# clock_led_face.net
KiCad netlist of a schematic drawn in Altium Designer
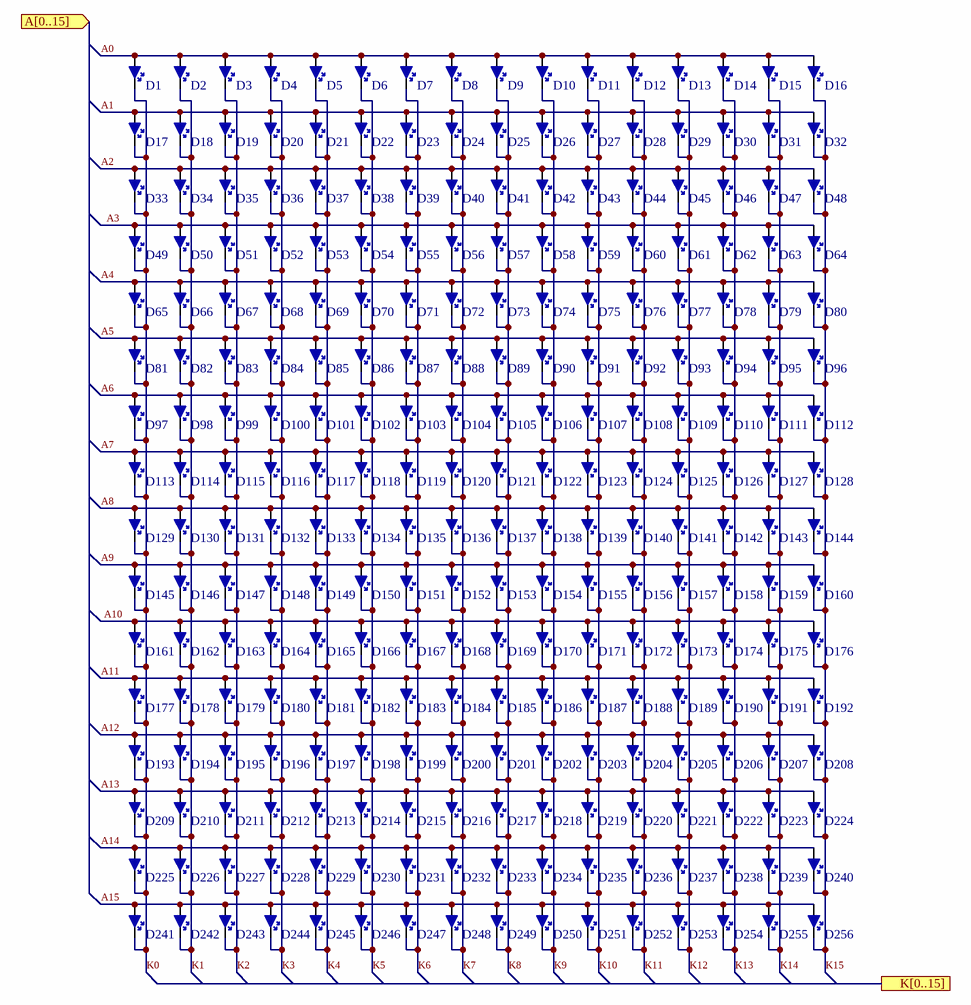
[diagram p0: clock_led_face.SchDoc]

(export (version "E")
  (design (tool "Eeschema 10.0.6"))
  (components
    (comp (ref "D1")
      (value "LED")
      (footprint "LED_0402")
      (description "Red 0402 SMD LED")
      (libsource (lib "") (part "LED_1"))
    )
    (comp (ref "D2")
      (value "LED")
      (footprint "LED_0402")
      (description "Red 0402 SMD LED")
      (libsource (lib "") (part "LED_1"))
    )
    (comp (ref "D3")
      (value "LED")
      (footprint "LED_0402")
      (description "Red 0402 SMD LED")
      (libsource (lib "") (part "LED_1"))
    )
    (comp (ref "D4")
      (value "LED")
      (footprint "LED_0402")
      (description "Red 0402 SMD LED")
      (libsource (lib "") (part "LED_1"))
    )
    (comp (ref "D5")
      (value "LED")
      (footprint "LED_0402")
      (description "Red 0402 SMD LED")
      (libsource (lib "") (part "LED_1"))
    )
    (comp (ref "D6")
      (value "LED")
      (footprint "LED_0402")
      (description "Red 0402 SMD LED")
      (libsource (lib "") (part "LED_1"))
    )
    (comp (ref "D7")
      (value "LED")
      (footprint "LED_0402")
      (description "Red 0402 SMD LED")
      (libsource (lib "") (part "LED_1"))
    )
    (comp (ref "D8")
      (value "LED")
      (footprint "LED_0402")
      (description "Red 0402 SMD LED")
      (libsource (lib "") (part "LED_1"))
    )
    (comp (ref "D9")
      (value "LED")
      (footprint "LED_0402")
      (description "Red 0402 SMD LED")
      (libsource (lib "") (part "LED_1"))
    )
    (comp (ref "D10")
      (value "LED")
      (footprint "LED_0402")
      (description "Red 0402 SMD LED")
      (libsource (lib "") (part "LED_1"))
    )
    (comp (ref "D11")
      (value "LED")
      (footprint "LED_0402")
      (description "Red 0402 SMD LED")
      (libsource (lib "") (part "LED_1"))
    )
    (comp (ref "D12")
      (value "LED")
      (footprint "LED_0402")
      (description "Red 0402 SMD LED")
      (libsource (lib "") (part "LED_1"))
    )
    (comp (ref "D13")
      (value "LED")
      (footprint "LED_0402")
      (description "Red 0402 SMD LED")
      (libsource (lib "") (part "LED_1"))
    )
    (comp (ref "D14")
      (value "LED")
      (footprint "LED_0402")
      (description "Red 0402 SMD LED")
      (libsource (lib "") (part "LED_1"))
    )
    (comp (ref "D15")
      (value "LED")
      (footprint "LED_0402")
      (description "Red 0402 SMD LED")
      (libsource (lib "") (part "LED_1"))
    )
    (comp (ref "D16")
      (value "LED")
      (footprint "LED_0402")
      (description "Red 0402 SMD LED")
      (libsource (lib "") (part "LED_1"))
    )
    (comp (ref "D17")
      (value "LED")
      (footprint "LED_0402")
      (description "Red 0402 SMD LED")
      (libsource (lib "") (part "LED_1"))
    )
    (comp (ref "D18")
      (value "LED")
      (footprint "LED_0402")
      (description "Red 0402 SMD LED")
      (libsource (lib "") (part "LED_1"))
    )
    (comp (ref "D19")
      (value "LED")
      (footprint "LED_0402")
      (description "Red 0402 SMD LED")
      (libsource (lib "") (part "LED_1"))
    )
    (comp (ref "D20")
      (value "LED")
      (footprint "LED_0402")
      (description "Red 0402 SMD LED")
      (libsource (lib "") (part "LED_1"))
    )
    (comp (ref "D21")
      (value "LED")
      (footprint "LED_0402")
      (description "Red 0402 SMD LED")
      (libsource (lib "") (part "LED_1"))
    )
    (comp (ref "D22")
      (value "LED")
      (footprint "LED_0402")
      (description "Red 0402 SMD LED")
      (libsource (lib "") (part "LED_1"))
    )
    (comp (ref "D23")
      (value "LED")
      (footprint "LED_0402")
      (description "Red 0402 SMD LED")
      (libsource (lib "") (part "LED_1"))
    )
    (comp (ref "D24")
      (value "LED")
      (footprint "LED_0402")
      (description "Red 0402 SMD LED")
      (libsource (lib "") (part "LED_1"))
    )
    (comp (ref "D25")
      (value "LED")
      (footprint "LED_0402")
      (description "Red 0402 SMD LED")
      (libsource (lib "") (part "LED_1"))
    )
    (comp (ref "D26")
      (value "LED")
      (footprint "LED_0402")
      (description "Red 0402 SMD LED")
      (libsource (lib "") (part "LED_1"))
    )
    (comp (ref "D27")
      (value "LED")
      (footprint "LED_0402")
      (description "Red 0402 SMD LED")
      (libsource (lib "") (part "LED_1"))
    )
    (comp (ref "D28")
      (value "LED")
      (footprint "LED_0402")
      (description "Red 0402 SMD LED")
      (libsource (lib "") (part "LED_1"))
    )
    (comp (ref "D29")
      (value "LED")
      (footprint "LED_0402")
      (description "Red 0402 SMD LED")
      (libsource (lib "") (part "LED_1"))
    )
    (comp (ref "D30")
      (value "LED")
      (footprint "LED_0402")
      (description "Red 0402 SMD LED")
      (libsource (lib "") (part "LED_1"))
    )
    (comp (ref "D31")
      (value "LED")
      (footprint "LED_0402")
      (description "Red 0402 SMD LED")
      (libsource (lib "") (part "LED_1"))
    )
    (comp (ref "D32")
      (value "LED")
      (footprint "LED_0402")
      (description "Red 0402 SMD LED")
      (libsource (lib "") (part "LED_1"))
    )
    (comp (ref "D33")
      (value "LED")
      (footprint "LED_0402")
      (description "Red 0402 SMD LED")
      (libsource (lib "") (part "LED_1"))
    )
    (comp (ref "D34")
      (value "LED")
      (footprint "LED_0402")
      (description "Red 0402 SMD LED")
      (libsource (lib "") (part "LED_1"))
    )
    (comp (ref "D35")
      (value "LED")
      (footprint "LED_0402")
      (description "Red 0402 SMD LED")
      (libsource (lib "") (part "LED_1"))
    )
    (comp (ref "D36")
      (value "LED")
      (footprint "LED_0402")
      (description "Red 0402 SMD LED")
      (libsource (lib "") (part "LED_1"))
    )
    (comp (ref "D37")
      (value "LED")
      (footprint "LED_0402")
      (description "Red 0402 SMD LED")
      (libsource (lib "") (part "LED_1"))
    )
    (comp (ref "D38")
      (value "LED")
      (footprint "LED_0402")
      (description "Red 0402 SMD LED")
      (libsource (lib "") (part "LED_1"))
    )
    (comp (ref "D39")
      (value "LED")
      (footprint "LED_0402")
      (description "Red 0402 SMD LED")
      (libsource (lib "") (part "LED_1"))
    )
    (comp (ref "D40")
      (value "LED")
      (footprint "LED_0402")
      (description "Red 0402 SMD LED")
      (libsource (lib "") (part "LED_1"))
    )
    (comp (ref "D41")
      (value "LED")
      (footprint "LED_0402")
      (description "Red 0402 SMD LED")
      (libsource (lib "") (part "LED_1"))
    )
    (comp (ref "D42")
      (value "LED")
      (footprint "LED_0402")
      (description "Red 0402 SMD LED")
      (libsource (lib "") (part "LED_1"))
    )
    (comp (ref "D43")
      (value "LED")
      (footprint "LED_0402")
      (description "Red 0402 SMD LED")
      (libsource (lib "") (part "LED_1"))
    )
    (comp (ref "D44")
      (value "LED")
      (footprint "LED_0402")
      (description "Red 0402 SMD LED")
      (libsource (lib "") (part "LED_1"))
    )
    (comp (ref "D45")
      (value "LED")
      (footprint "LED_0402")
      (description "Red 0402 SMD LED")
      (libsource (lib "") (part "LED_1"))
    )
    (comp (ref "D46")
      (value "LED")
      (footprint "LED_0402")
      (description "Red 0402 SMD LED")
      (libsource (lib "") (part "LED_1"))
    )
    (comp (ref "D47")
      (value "LED")
      (footprint "LED_0402")
      (description "Red 0402 SMD LED")
      (libsource (lib "") (part "LED_1"))
    )
    (comp (ref "D48")
      (value "LED")
      (footprint "LED_0402")
      (description "Red 0402 SMD LED")
      (libsource (lib "") (part "LED_1"))
    )
    (comp (ref "D49")
      (value "LED")
      (footprint "LED_0402")
      (description "Red 0402 SMD LED")
      (libsource (lib "") (part "LED_1"))
    )
    (comp (ref "D50")
      (value "LED")
      (footprint "LED_0402")
      (description "Red 0402 SMD LED")
      (libsource (lib "") (part "LED_1"))
    )
    (comp (ref "D51")
      (value "LED")
      (footprint "LED_0402")
      (description "Red 0402 SMD LED")
      (libsource (lib "") (part "LED_1"))
    )
    (comp (ref "D52")
      (value "LED")
      (footprint "LED_0402")
      (description "Red 0402 SMD LED")
      (libsource (lib "") (part "LED_1"))
    )
    (comp (ref "D53")
      (value "LED")
      (footprint "LED_0402")
      (description "Red 0402 SMD LED")
      (libsource (lib "") (part "LED_1"))
    )
    (comp (ref "D54")
      (value "LED")
      (footprint "LED_0402")
      (description "Red 0402 SMD LED")
      (libsource (lib "") (part "LED_1"))
    )
    (comp (ref "D55")
      (value "LED")
      (footprint "LED_0402")
      (description "Red 0402 SMD LED")
      (libsource (lib "") (part "LED_1"))
    )
    (comp (ref "D56")
      (value "LED")
      (footprint "LED_0402")
      (description "Red 0402 SMD LED")
      (libsource (lib "") (part "LED_1"))
    )
    (comp (ref "D57")
      (value "LED")
      (footprint "LED_0402")
      (description "Red 0402 SMD LED")
      (libsource (lib "") (part "LED_1"))
    )
    (comp (ref "D58")
      (value "LED")
      (footprint "LED_0402")
      (description "Red 0402 SMD LED")
      (libsource (lib "") (part "LED_1"))
    )
    (comp (ref "D59")
      (value "LED")
      (footprint "LED_0402")
      (description "Red 0402 SMD LED")
      (libsource (lib "") (part "LED_1"))
    )
    (comp (ref "D60")
      (value "LED")
      (footprint "LED_0402")
      (description "Red 0402 SMD LED")
      (libsource (lib "") (part "LED_1"))
    )
    (comp (ref "D61")
      (value "LED")
      (footprint "LED_0402")
      (description "Red 0402 SMD LED")
      (libsource (lib "") (part "LED_1"))
    )
    (comp (ref "D62")
      (value "LED")
      (footprint "LED_0402")
      (description "Red 0402 SMD LED")
      (libsource (lib "") (part "LED_1"))
    )
    (comp (ref "D63")
      (value "LED")
      (footprint "LED_0402")
      (description "Red 0402 SMD LED")
      (libsource (lib "") (part "LED_1"))
    )
    (comp (ref "D64")
      (value "LED")
      (footprint "LED_0402")
      (description "Red 0402 SMD LED")
      (libsource (lib "") (part "LED_1"))
    )
    (comp (ref "D65")
      (value "LED")
      (footprint "LED_0402")
      (description "Red 0402 SMD LED")
      (libsource (lib "") (part "LED_1"))
    )
    (comp (ref "D66")
      (value "LED")
      (footprint "LED_0402")
      (description "Red 0402 SMD LED")
      (libsource (lib "") (part "LED_1"))
    )
    (comp (ref "D67")
      (value "LED")
      (footprint "LED_0402")
      (description "Red 0402 SMD LED")
      (libsource (lib "") (part "LED_1"))
    )
    (comp (ref "D68")
      (value "LED")
      (footprint "LED_0402")
      (description "Red 0402 SMD LED")
      (libsource (lib "") (part "LED_1"))
    )
    (comp (ref "D69")
      (value "LED")
      (footprint "LED_0402")
      (description "Red 0402 SMD LED")
      (libsource (lib "") (part "LED_1"))
    )
    (comp (ref "D70")
      (value "LED")
      (footprint "LED_0402")
      (description "Red 0402 SMD LED")
      (libsource (lib "") (part "LED_1"))
    )
    (comp (ref "D71")
      (value "LED")
      (footprint "LED_0402")
      (description "Red 0402 SMD LED")
      (libsource (lib "") (part "LED_1"))
    )
    (comp (ref "D72")
      (value "LED")
      (footprint "LED_0402")
      (description "Red 0402 SMD LED")
      (libsource (lib "") (part "LED_1"))
    )
    (comp (ref "D73")
      (value "LED")
      (footprint "LED_0402")
      (description "Red 0402 SMD LED")
      (libsource (lib "") (part "LED_1"))
    )
    (comp (ref "D74")
      (value "LED")
      (footprint "LED_0402")
      (description "Red 0402 SMD LED")
      (libsource (lib "") (part "LED_1"))
    )
    (comp (ref "D75")
      (value "LED")
      (footprint "LED_0402")
      (description "Red 0402 SMD LED")
      (libsource (lib "") (part "LED_1"))
    )
    (comp (ref "D76")
      (value "LED")
      (footprint "LED_0402")
      (description "Red 0402 SMD LED")
      (libsource (lib "") (part "LED_1"))
    )
    (comp (ref "D77")
      (value "LED")
      (footprint "LED_0402")
      (description "Red 0402 SMD LED")
      (libsource (lib "") (part "LED_1"))
    )
    (comp (ref "D78")
      (value "LED")
      (footprint "LED_0402")
      (description "Red 0402 SMD LED")
      (libsource (lib "") (part "LED_1"))
    )
    (comp (ref "D79")
      (value "LED")
      (footprint "LED_0402")
      (description "Red 0402 SMD LED")
      (libsource (lib "") (part "LED_1"))
    )
    (comp (ref "D80")
      (value "LED")
      (footprint "LED_0402")
      (description "Red 0402 SMD LED")
      (libsource (lib "") (part "LED_1"))
    )
    (comp (ref "D81")
      (value "LED")
      (footprint "LED_0402")
      (description "Red 0402 SMD LED")
      (libsource (lib "") (part "LED_1"))
    )
    (comp (ref "D82")
      (value "LED")
      (footprint "LED_0402")
      (description "Red 0402 SMD LED")
      (libsource (lib "") (part "LED_1"))
    )
    (comp (ref "D83")
      (value "LED")
      (footprint "LED_0402")
      (description "Red 0402 SMD LED")
      (libsource (lib "") (part "LED_1"))
    )
    (comp (ref "D84")
      (value "LED")
      (footprint "LED_0402")
      (description "Red 0402 SMD LED")
      (libsource (lib "") (part "LED_1"))
    )
    (comp (ref "D85")
      (value "LED")
      (footprint "LED_0402")
      (description "Red 0402 SMD LED")
      (libsource (lib "") (part "LED_1"))
    )
    (comp (ref "D86")
      (value "LED")
      (footprint "LED_0402")
      (description "Red 0402 SMD LED")
      (libsource (lib "") (part "LED_1"))
    )
    (comp (ref "D87")
      (value "LED")
      (footprint "LED_0402")
      (description "Red 0402 SMD LED")
      (libsource (lib "") (part "LED_1"))
    )
    (comp (ref "D88")
      (value "LED")
      (footprint "LED_0402")
      (description "Red 0402 SMD LED")
      (libsource (lib "") (part "LED_1"))
    )
    (comp (ref "D89")
      (value "LED")
      (footprint "LED_0402")
      (description "Red 0402 SMD LED")
      (libsource (lib "") (part "LED_1"))
    )
    (comp (ref "D90")
      (value "LED")
      (footprint "LED_0402")
      (description "Red 0402 SMD LED")
      (libsource (lib "") (part "LED_1"))
    )
    (comp (ref "D91")
      (value "LED")
      (footprint "LED_0402")
      (description "Red 0402 SMD LED")
      (libsource (lib "") (part "LED_1"))
    )
    (comp (ref "D92")
      (value "LED")
      (footprint "LED_0402")
      (description "Red 0402 SMD LED")
      (libsource (lib "") (part "LED_1"))
    )
    (comp (ref "D93")
      (value "LED")
      (footprint "LED_0402")
      (description "Red 0402 SMD LED")
      (libsource (lib "") (part "LED_1"))
    )
    (comp (ref "D94")
      (value "LED")
      (footprint "LED_0402")
      (description "Red 0402 SMD LED")
      (libsource (lib "") (part "LED_1"))
    )
    (comp (ref "D95")
      (value "LED")
      (footprint "LED_0402")
      (description "Red 0402 SMD LED")
      (libsource (lib "") (part "LED_1"))
    )
    (comp (ref "D96")
      (value "LED")
      (footprint "LED_0402")
      (description "Red 0402 SMD LED")
      (libsource (lib "") (part "LED_1"))
    )
    (comp (ref "D97")
      (value "LED")
      (footprint "LED_0402")
      (description "Red 0402 SMD LED")
      (libsource (lib "") (part "LED_1"))
    )
    (comp (ref "D98")
      (value "LED")
      (footprint "LED_0402")
      (description "Red 0402 SMD LED")
      (libsource (lib "") (part "LED_1"))
    )
    (comp (ref "D99")
      (value "LED")
      (footprint "LED_0402")
      (description "Red 0402 SMD LED")
      (libsource (lib "") (part "LED_1"))
    )
    (comp (ref "D100")
      (value "LED")
      (footprint "LED_0402")
      (description "Red 0402 SMD LED")
      (libsource (lib "") (part "LED_1"))
    )
    (comp (ref "D101")
      (value "LED")
      (footprint "LED_0402")
      (description "Red 0402 SMD LED")
      (libsource (lib "") (part "LED_1"))
    )
    (comp (ref "D102")
      (value "LED")
      (footprint "LED_0402")
      (description "Red 0402 SMD LED")
      (libsource (lib "") (part "LED_1"))
    )
    (comp (ref "D103")
      (value "LED")
      (footprint "LED_0402")
      (description "Red 0402 SMD LED")
      (libsource (lib "") (part "LED_1"))
    )
    (comp (ref "D104")
      (value "LED")
      (footprint "LED_0402")
      (description "Red 0402 SMD LED")
      (libsource (lib "") (part "LED_1"))
    )
    (comp (ref "D105")
      (value "LED")
      (footprint "LED_0402")
      (description "Red 0402 SMD LED")
      (libsource (lib "") (part "LED_1"))
    )
    (comp (ref "D106")
      (value "LED")
      (footprint "LED_0402")
      (description "Red 0402 SMD LED")
      (libsource (lib "") (part "LED_1"))
    )
    (comp (ref "D107")
      (value "LED")
      (footprint "LED_0402")
      (description "Red 0402 SMD LED")
      (libsource (lib "") (part "LED_1"))
    )
    (comp (ref "D108")
      (value "LED")
      (footprint "LED_0402")
      (description "Red 0402 SMD LED")
      (libsource (lib "") (part "LED_1"))
    )
    (comp (ref "D109")
      (value "LED")
      (footprint "LED_0402")
      (description "Red 0402 SMD LED")
      (libsource (lib "") (part "LED_1"))
    )
    (comp (ref "D110")
      (value "LED")
      (footprint "LED_0402")
      (description "Red 0402 SMD LED")
      (libsource (lib "") (part "LED_1"))
    )
    (comp (ref "D111")
      (value "LED")
      (footprint "LED_0402")
      (description "Red 0402 SMD LED")
      (libsource (lib "") (part "LED_1"))
    )
    (comp (ref "D112")
      (value "LED")
      (footprint "LED_0402")
      (description "Red 0402 SMD LED")
      (libsource (lib "") (part "LED_1"))
    )
    (comp (ref "D113")
      (value "LED")
      (footprint "LED_0402")
      (description "Red 0402 SMD LED")
      (libsource (lib "") (part "LED_1"))
    )
    (comp (ref "D114")
      (value "LED")
      (footprint "LED_0402")
      (description "Red 0402 SMD LED")
      (libsource (lib "") (part "LED_1"))
    )
    (comp (ref "D115")
      (value "LED")
      (footprint "LED_0402")
      (description "Red 0402 SMD LED")
      (libsource (lib "") (part "LED_1"))
    )
    (comp (ref "D116")
      (value "LED")
      (footprint "LED_0402")
      (description "Red 0402 SMD LED")
      (libsource (lib "") (part "LED_1"))
    )
    (comp (ref "D117")
      (value "LED")
      (footprint "LED_0402")
      (description "Red 0402 SMD LED")
      (libsource (lib "") (part "LED_1"))
    )
    (comp (ref "D118")
      (value "LED")
      (footprint "LED_0402")
      (description "Red 0402 SMD LED")
      (libsource (lib "") (part "LED_1"))
    )
    (comp (ref "D119")
      (value "LED")
      (footprint "LED_0402")
      (description "Red 0402 SMD LED")
      (libsource (lib "") (part "LED_1"))
    )
    (comp (ref "D120")
      (value "LED")
      (footprint "LED_0402")
      (description "Red 0402 SMD LED")
      (libsource (lib "") (part "LED_1"))
    )
    (comp (ref "D121")
      (value "LED")
      (footprint "LED_0402")
      (description "Red 0402 SMD LED")
      (libsource (lib "") (part "LED_1"))
    )
    (comp (ref "D122")
      (value "LED")
      (footprint "LED_0402")
      (description "Red 0402 SMD LED")
      (libsource (lib "") (part "LED_1"))
    )
    (comp (ref "D123")
      (value "LED")
      (footprint "LED_0402")
      (description "Red 0402 SMD LED")
      (libsource (lib "") (part "LED_1"))
    )
    (comp (ref "D124")
      (value "LED")
      (footprint "LED_0402")
      (description "Red 0402 SMD LED")
      (libsource (lib "") (part "LED_1"))
    )
    (comp (ref "D125")
      (value "LED")
      (footprint "LED_0402")
      (description "Red 0402 SMD LED")
      (libsource (lib "") (part "LED_1"))
    )
    (comp (ref "D126")
      (value "LED")
      (footprint "LED_0402")
      (description "Red 0402 SMD LED")
      (libsource (lib "") (part "LED_1"))
    )
    (comp (ref "D127")
      (value "LED")
      (footprint "LED_0402")
      (description "Red 0402 SMD LED")
      (libsource (lib "") (part "LED_1"))
    )
    (comp (ref "D128")
      (value "LED")
      (footprint "LED_0402")
      (description "Red 0402 SMD LED")
      (libsource (lib "") (part "LED_1"))
    )
    (comp (ref "D129")
      (value "LED")
      (footprint "LED_0402")
      (description "Red 0402 SMD LED")
      (libsource (lib "") (part "LED_1"))
    )
    (comp (ref "D130")
      (value "LED")
      (footprint "LED_0402")
      (description "Red 0402 SMD LED")
      (libsource (lib "") (part "LED_1"))
    )
    (comp (ref "D131")
      (value "LED")
      (footprint "LED_0402")
      (description "Red 0402 SMD LED")
      (libsource (lib "") (part "LED_1"))
    )
    (comp (ref "D132")
      (value "LED")
      (footprint "LED_0402")
      (description "Red 0402 SMD LED")
      (libsource (lib "") (part "LED_1"))
    )
    (comp (ref "D133")
      (value "LED")
      (footprint "LED_0402")
      (description "Red 0402 SMD LED")
      (libsource (lib "") (part "LED_1"))
    )
    (comp (ref "D134")
      (value "LED")
      (footprint "LED_0402")
      (description "Red 0402 SMD LED")
      (libsource (lib "") (part "LED_1"))
    )
    (comp (ref "D135")
      (value "LED")
      (footprint "LED_0402")
      (description "Red 0402 SMD LED")
      (libsource (lib "") (part "LED_1"))
    )
    (comp (ref "D136")
      (value "LED")
      (footprint "LED_0402")
      (description "Red 0402 SMD LED")
      (libsource (lib "") (part "LED_1"))
    )
    (comp (ref "D137")
      (value "LED")
      (footprint "LED_0402")
      (description "Red 0402 SMD LED")
      (libsource (lib "") (part "LED_1"))
    )
    (comp (ref "D138")
      (value "LED")
      (footprint "LED_0402")
      (description "Red 0402 SMD LED")
      (libsource (lib "") (part "LED_1"))
    )
    (comp (ref "D139")
      (value "LED")
      (footprint "LED_0402")
      (description "Red 0402 SMD LED")
      (libsource (lib "") (part "LED_1"))
    )
    (comp (ref "D140")
      (value "LED")
      (footprint "LED_0402")
      (description "Red 0402 SMD LED")
      (libsource (lib "") (part "LED_1"))
    )
    (comp (ref "D141")
      (value "LED")
      (footprint "LED_0402")
      (description "Red 0402 SMD LED")
      (libsource (lib "") (part "LED_1"))
    )
    (comp (ref "D142")
      (value "LED")
      (footprint "LED_0402")
      (description "Red 0402 SMD LED")
      (libsource (lib "") (part "LED_1"))
    )
    (comp (ref "D143")
      (value "LED")
      (footprint "LED_0402")
      (description "Red 0402 SMD LED")
      (libsource (lib "") (part "LED_1"))
    )
    (comp (ref "D144")
      (value "LED")
      (footprint "LED_0402")
      (description "Red 0402 SMD LED")
      (libsource (lib "") (part "LED_1"))
    )
    (comp (ref "D145")
      (value "LED")
      (footprint "LED_0402")
      (description "Red 0402 SMD LED")
      (libsource (lib "") (part "LED_1"))
    )
    (comp (ref "D146")
      (value "LED")
      (footprint "LED_0402")
      (description "Red 0402 SMD LED")
      (libsource (lib "") (part "LED_1"))
    )
    (comp (ref "D147")
      (value "LED")
      (footprint "LED_0402")
      (description "Red 0402 SMD LED")
      (libsource (lib "") (part "LED_1"))
    )
    (comp (ref "D148")
      (value "LED")
      (footprint "LED_0402")
      (description "Red 0402 SMD LED")
      (libsource (lib "") (part "LED_1"))
    )
    (comp (ref "D149")
      (value "LED")
      (footprint "LED_0402")
      (description "Red 0402 SMD LED")
      (libsource (lib "") (part "LED_1"))
    )
    (comp (ref "D150")
      (value "LED")
      (footprint "LED_0402")
      (description "Red 0402 SMD LED")
      (libsource (lib "") (part "LED_1"))
    )
    (comp (ref "D151")
      (value "LED")
      (footprint "LED_0402")
      (description "Red 0402 SMD LED")
      (libsource (lib "") (part "LED_1"))
    )
    (comp (ref "D152")
      (value "LED")
      (footprint "LED_0402")
      (description "Red 0402 SMD LED")
      (libsource (lib "") (part "LED_1"))
    )
    (comp (ref "D153")
      (value "LED")
      (footprint "LED_0402")
      (description "Red 0402 SMD LED")
      (libsource (lib "") (part "LED_1"))
    )
    (comp (ref "D154")
      (value "LED")
      (footprint "LED_0402")
      (description "Red 0402 SMD LED")
      (libsource (lib "") (part "LED_1"))
    )
    (comp (ref "D155")
      (value "LED")
      (footprint "LED_0402")
      (description "Red 0402 SMD LED")
      (libsource (lib "") (part "LED_1"))
    )
    (comp (ref "D156")
      (value "LED")
      (footprint "LED_0402")
      (description "Red 0402 SMD LED")
      (libsource (lib "") (part "LED_1"))
    )
    (comp (ref "D157")
      (value "LED")
      (footprint "LED_0402")
      (description "Red 0402 SMD LED")
      (libsource (lib "") (part "LED_1"))
    )
    (comp (ref "D158")
      (value "LED")
      (footprint "LED_0402")
      (description "Red 0402 SMD LED")
      (libsource (lib "") (part "LED_1"))
    )
    (comp (ref "D159")
      (value "LED")
      (footprint "LED_0402")
      (description "Red 0402 SMD LED")
      (libsource (lib "") (part "LED_1"))
    )
    (comp (ref "D160")
      (value "LED")
      (footprint "LED_0402")
      (description "Red 0402 SMD LED")
      (libsource (lib "") (part "LED_1"))
    )
    (comp (ref "D161")
      (value "LED")
      (footprint "LED_0402")
      (description "Red 0402 SMD LED")
      (libsource (lib "") (part "LED_1"))
    )
    (comp (ref "D162")
      (value "LED")
      (footprint "LED_0402")
      (description "Red 0402 SMD LED")
      (libsource (lib "") (part "LED_1"))
    )
    (comp (ref "D163")
      (value "LED")
      (footprint "LED_0402")
      (description "Red 0402 SMD LED")
      (libsource (lib "") (part "LED_1"))
    )
    (comp (ref "D164")
      (value "LED")
      (footprint "LED_0402")
      (description "Red 0402 SMD LED")
      (libsource (lib "") (part "LED_1"))
    )
    (comp (ref "D165")
      (value "LED")
      (footprint "LED_0402")
      (description "Red 0402 SMD LED")
      (libsource (lib "") (part "LED_1"))
    )
    (comp (ref "D166")
      (value "LED")
      (footprint "LED_0402")
      (description "Red 0402 SMD LED")
      (libsource (lib "") (part "LED_1"))
    )
    (comp (ref "D167")
      (value "LED")
      (footprint "LED_0402")
      (description "Red 0402 SMD LED")
      (libsource (lib "") (part "LED_1"))
    )
    (comp (ref "D168")
      (value "LED")
      (footprint "LED_0402")
      (description "Red 0402 SMD LED")
      (libsource (lib "") (part "LED_1"))
    )
    (comp (ref "D169")
      (value "LED")
      (footprint "LED_0402")
      (description "Red 0402 SMD LED")
      (libsource (lib "") (part "LED_1"))
    )
    (comp (ref "D170")
      (value "LED")
      (footprint "LED_0402")
      (description "Red 0402 SMD LED")
      (libsource (lib "") (part "LED_1"))
    )
    (comp (ref "D171")
      (value "LED")
      (footprint "LED_0402")
      (description "Red 0402 SMD LED")
      (libsource (lib "") (part "LED_1"))
    )
    (comp (ref "D172")
      (value "LED")
      (footprint "LED_0402")
      (description "Red 0402 SMD LED")
      (libsource (lib "") (part "LED_1"))
    )
    (comp (ref "D173")
      (value "LED")
      (footprint "LED_0402")
      (description "Red 0402 SMD LED")
      (libsource (lib "") (part "LED_1"))
    )
    (comp (ref "D174")
      (value "LED")
      (footprint "LED_0402")
      (description "Red 0402 SMD LED")
      (libsource (lib "") (part "LED_1"))
    )
    (comp (ref "D175")
      (value "LED")
      (footprint "LED_0402")
      (description "Red 0402 SMD LED")
      (libsource (lib "") (part "LED_1"))
    )
    (comp (ref "D176")
      (value "LED")
      (footprint "LED_0402")
      (description "Red 0402 SMD LED")
      (libsource (lib "") (part "LED_1"))
    )
    (comp (ref "D177")
      (value "LED")
      (footprint "LED_0402")
      (description "Red 0402 SMD LED")
      (libsource (lib "") (part "LED_1"))
    )
    (comp (ref "D178")
      (value "LED")
      (footprint "LED_0402")
      (description "Red 0402 SMD LED")
      (libsource (lib "") (part "LED_1"))
    )
    (comp (ref "D179")
      (value "LED")
      (footprint "LED_0402")
      (description "Red 0402 SMD LED")
      (libsource (lib "") (part "LED_1"))
    )
    (comp (ref "D180")
      (value "LED")
      (footprint "LED_0402")
      (description "Red 0402 SMD LED")
      (libsource (lib "") (part "LED_1"))
    )
    (comp (ref "D181")
      (value "LED")
      (footprint "LED_0402")
      (description "Red 0402 SMD LED")
      (libsource (lib "") (part "LED_1"))
    )
    (comp (ref "D182")
      (value "LED")
      (footprint "LED_0402")
      (description "Red 0402 SMD LED")
      (libsource (lib "") (part "LED_1"))
    )
    (comp (ref "D183")
      (value "LED")
      (footprint "LED_0402")
      (description "Red 0402 SMD LED")
      (libsource (lib "") (part "LED_1"))
    )
    (comp (ref "D184")
      (value "LED")
      (footprint "LED_0402")
      (description "Red 0402 SMD LED")
      (libsource (lib "") (part "LED_1"))
    )
    (comp (ref "D185")
      (value "LED")
      (footprint "LED_0402")
      (description "Red 0402 SMD LED")
      (libsource (lib "") (part "LED_1"))
    )
    (comp (ref "D186")
      (value "LED")
      (footprint "LED_0402")
      (description "Red 0402 SMD LED")
      (libsource (lib "") (part "LED_1"))
    )
    (comp (ref "D187")
      (value "LED")
      (footprint "LED_0402")
      (description "Red 0402 SMD LED")
      (libsource (lib "") (part "LED_1"))
    )
    (comp (ref "D188")
      (value "LED")
      (footprint "LED_0402")
      (description "Red 0402 SMD LED")
      (libsource (lib "") (part "LED_1"))
    )
    (comp (ref "D189")
      (value "LED")
      (footprint "LED_0402")
      (description "Red 0402 SMD LED")
      (libsource (lib "") (part "LED_1"))
    )
    (comp (ref "D190")
      (value "LED")
      (footprint "LED_0402")
      (description "Red 0402 SMD LED")
      (libsource (lib "") (part "LED_1"))
    )
    (comp (ref "D191")
      (value "LED")
      (footprint "LED_0402")
      (description "Red 0402 SMD LED")
      (libsource (lib "") (part "LED_1"))
    )
    (comp (ref "D192")
      (value "LED")
      (footprint "LED_0402")
      (description "Red 0402 SMD LED")
      (libsource (lib "") (part "LED_1"))
    )
    (comp (ref "D193")
      (value "LED")
      (footprint "LED_0402")
      (description "Red 0402 SMD LED")
      (libsource (lib "") (part "LED_1"))
    )
    (comp (ref "D194")
      (value "LED")
      (footprint "LED_0402")
      (description "Red 0402 SMD LED")
      (libsource (lib "") (part "LED_1"))
    )
    (comp (ref "D195")
      (value "LED")
      (footprint "LED_0402")
      (description "Red 0402 SMD LED")
      (libsource (lib "") (part "LED_1"))
    )
    (comp (ref "D196")
      (value "LED")
      (footprint "LED_0402")
      (description "Red 0402 SMD LED")
      (libsource (lib "") (part "LED_1"))
    )
    (comp (ref "D197")
      (value "LED")
      (footprint "LED_0402")
      (description "Red 0402 SMD LED")
      (libsource (lib "") (part "LED_1"))
    )
    (comp (ref "D198")
      (value "LED")
      (footprint "LED_0402")
      (description "Red 0402 SMD LED")
      (libsource (lib "") (part "LED_1"))
    )
    (comp (ref "D199")
      (value "LED")
      (footprint "LED_0402")
      (description "Red 0402 SMD LED")
      (libsource (lib "") (part "LED_1"))
    )
    (comp (ref "D200")
      (value "LED")
      (footprint "LED_0402")
      (description "Red 0402 SMD LED")
      (libsource (lib "") (part "LED_1"))
    )
    (comp (ref "D201")
      (value "LED")
      (footprint "LED_0402")
      (description "Red 0402 SMD LED")
      (libsource (lib "") (part "LED_1"))
    )
    (comp (ref "D202")
      (value "LED")
      (footprint "LED_0402")
      (description "Red 0402 SMD LED")
      (libsource (lib "") (part "LED_1"))
    )
    (comp (ref "D203")
      (value "LED")
      (footprint "LED_0402")
      (description "Red 0402 SMD LED")
      (libsource (lib "") (part "LED_1"))
    )
    (comp (ref "D204")
      (value "LED")
      (footprint "LED_0402")
      (description "Red 0402 SMD LED")
      (libsource (lib "") (part "LED_1"))
    )
    (comp (ref "D205")
      (value "LED")
      (footprint "LED_0402")
      (description "Red 0402 SMD LED")
      (libsource (lib "") (part "LED_1"))
    )
    (comp (ref "D206")
      (value "LED")
      (footprint "LED_0402")
      (description "Red 0402 SMD LED")
      (libsource (lib "") (part "LED_1"))
    )
    (comp (ref "D207")
      (value "LED")
      (footprint "LED_0402")
      (description "Red 0402 SMD LED")
      (libsource (lib "") (part "LED_1"))
    )
    (comp (ref "D208")
      (value "LED")
      (footprint "LED_0402")
      (description "Red 0402 SMD LED")
      (libsource (lib "") (part "LED_1"))
    )
    (comp (ref "D209")
      (value "LED")
      (footprint "LED_0402")
      (description "Red 0402 SMD LED")
      (libsource (lib "clock_led") (part "LED"))
    )
    (comp (ref "D210")
      (value "LED")
      (footprint "LED_0402")
      (description "Red 0402 SMD LED")
      (libsource (lib "clock_led") (part "LED"))
    )
    (comp (ref "D211")
      (value "LED")
      (footprint "LED_0402")
      (description "Red 0402 SMD LED")
      (libsource (lib "clock_led") (part "LED"))
    )
    (comp (ref "D212")
      (value "LED")
      (footprint "LED_0402")
      (description "Red 0402 SMD LED")
      (libsource (lib "clock_led") (part "LED"))
    )
    (comp (ref "D213")
      (value "LED")
      (footprint "LED_0402")
      (description "Red 0402 SMD LED")
      (libsource (lib "clock_led") (part "LED"))
    )
    (comp (ref "D214")
      (value "LED")
      (footprint "LED_0402")
      (description "Red 0402 SMD LED")
      (libsource (lib "clock_led") (part "LED"))
    )
    (comp (ref "D215")
      (value "LED")
      (footprint "LED_0402")
      (description "Red 0402 SMD LED")
      (libsource (lib "clock_led") (part "LED"))
    )
    (comp (ref "D216")
      (value "LED")
      (footprint "LED_0402")
      (description "Red 0402 SMD LED")
      (libsource (lib "clock_led") (part "LED"))
    )
    (comp (ref "D217")
      (value "LED")
      (footprint "LED_0402")
      (description "Red 0402 SMD LED")
      (libsource (lib "clock_led") (part "LED"))
    )
    (comp (ref "D218")
      (value "LED")
      (footprint "LED_0402")
      (description "Red 0402 SMD LED")
      (libsource (lib "clock_led") (part "LED"))
    )
    (comp (ref "D219")
      (value "LED")
      (footprint "LED_0402")
      (description "Red 0402 SMD LED")
      (libsource (lib "clock_led") (part "LED"))
    )
    (comp (ref "D220")
      (value "LED")
      (footprint "LED_0402")
      (description "Red 0402 SMD LED")
      (libsource (lib "clock_led") (part "LED"))
    )
    (comp (ref "D221")
      (value "LED")
      (footprint "LED_0402")
      (description "Red 0402 SMD LED")
      (libsource (lib "clock_led") (part "LED"))
    )
    (comp (ref "D222")
      (value "LED")
      (footprint "LED_0402")
      (description "Red 0402 SMD LED")
      (libsource (lib "clock_led") (part "LED"))
    )
    (comp (ref "D223")
      (value "LED")
      (footprint "LED_0402")
      (description "Red 0402 SMD LED")
      (libsource (lib "clock_led") (part "LED"))
    )
    (comp (ref "D224")
      (value "LED")
      (footprint "LED_0402")
      (description "Red 0402 SMD LED")
      (libsource (lib "clock_led") (part "LED"))
    )
    (comp (ref "D225")
      (value "LED")
      (footprint "LED_0402")
      (description "Red 0402 SMD LED")
      (libsource (lib "") (part "LED_2"))
    )
    (comp (ref "D226")
      (value "LED")
      (footprint "LED_0402")
      (description "Red 0402 SMD LED")
      (libsource (lib "") (part "LED_2"))
    )
    (comp (ref "D227")
      (value "LED")
      (footprint "LED_0402")
      (description "Red 0402 SMD LED")
      (libsource (lib "") (part "LED_2"))
    )
    (comp (ref "D228")
      (value "LED")
      (footprint "LED_0402")
      (description "Red 0402 SMD LED")
      (libsource (lib "") (part "LED_2"))
    )
    (comp (ref "D229")
      (value "LED")
      (footprint "LED_0402")
      (description "Red 0402 SMD LED")
      (libsource (lib "") (part "LED_2"))
    )
    (comp (ref "D230")
      (value "LED")
      (footprint "LED_0402")
      (description "Red 0402 SMD LED")
      (libsource (lib "") (part "LED_2"))
    )
    (comp (ref "D231")
      (value "LED")
      (footprint "LED_0402")
      (description "Red 0402 SMD LED")
      (libsource (lib "") (part "LED_2"))
    )
    (comp (ref "D232")
      (value "LED")
      (footprint "LED_0402")
      (description "Red 0402 SMD LED")
      (libsource (lib "") (part "LED_2"))
    )
    (comp (ref "D233")
      (value "LED")
      (footprint "LED_0402")
      (description "Red 0402 SMD LED")
      (libsource (lib "") (part "LED_2"))
    )
    (comp (ref "D234")
      (value "LED")
      (footprint "LED_0402")
      (description "Red 0402 SMD LED")
      (libsource (lib "") (part "LED_2"))
    )
    (comp (ref "D235")
      (value "LED")
      (footprint "LED_0402")
      (description "Red 0402 SMD LED")
      (libsource (lib "") (part "LED_2"))
    )
    (comp (ref "D236")
      (value "LED")
      (footprint "LED_0402")
      (description "Red 0402 SMD LED")
      (libsource (lib "") (part "LED_2"))
    )
    (comp (ref "D237")
      (value "LED")
      (footprint "LED_0402")
      (description "Red 0402 SMD LED")
      (libsource (lib "") (part "LED_2"))
    )
    (comp (ref "D238")
      (value "LED")
      (footprint "LED_0402")
      (description "Red 0402 SMD LED")
      (libsource (lib "") (part "LED_2"))
    )
    (comp (ref "D239")
      (value "LED")
      (footprint "LED_0402")
      (description "Red 0402 SMD LED")
      (libsource (lib "") (part "LED_2"))
    )
    (comp (ref "D240")
      (value "LED")
      (footprint "LED_0402")
      (description "Red 0402 SMD LED")
      (libsource (lib "") (part "LED_2"))
    )
    (comp (ref "D241")
      (value "LED")
      (footprint "LED_0402")
      (description "Red 0402 SMD LED")
      (libsource (lib "") (part "LED_2"))
    )
    (comp (ref "D242")
      (value "LED")
      (footprint "LED_0402")
      (description "Red 0402 SMD LED")
      (libsource (lib "") (part "LED_2"))
    )
    (comp (ref "D243")
      (value "LED")
      (footprint "LED_0402")
      (description "Red 0402 SMD LED")
      (libsource (lib "") (part "LED_2"))
    )
    (comp (ref "D244")
      (value "LED")
      (footprint "LED_0402")
      (description "Red 0402 SMD LED")
      (libsource (lib "") (part "LED_2"))
    )
    (comp (ref "D245")
      (value "LED")
      (footprint "LED_0402")
      (description "Red 0402 SMD LED")
      (libsource (lib "") (part "LED_2"))
    )
    (comp (ref "D246")
      (value "LED")
      (footprint "LED_0402")
      (description "Red 0402 SMD LED")
      (libsource (lib "") (part "LED_2"))
    )
    (comp (ref "D247")
      (value "LED")
      (footprint "LED_0402")
      (description "Red 0402 SMD LED")
      (libsource (lib "") (part "LED_2"))
    )
    (comp (ref "D248")
      (value "LED")
      (footprint "LED_0402")
      (description "Red 0402 SMD LED")
      (libsource (lib "") (part "LED_2"))
    )
    (comp (ref "D249")
      (value "LED")
      (footprint "LED_0402")
      (description "Red 0402 SMD LED")
      (libsource (lib "") (part "LED_2"))
    )
    (comp (ref "D250")
      (value "LED")
      (footprint "LED_0402")
      (description "Red 0402 SMD LED")
      (libsource (lib "") (part "LED_2"))
    )
    (comp (ref "D251")
      (value "LED")
      (footprint "LED_0402")
      (description "Red 0402 SMD LED")
      (libsource (lib "") (part "LED_2"))
    )
    (comp (ref "D252")
      (value "LED")
      (footprint "LED_0402")
      (description "Red 0402 SMD LED")
      (libsource (lib "") (part "LED_2"))
    )
    (comp (ref "D253")
      (value "LED")
      (footprint "LED_0402")
      (description "Red 0402 SMD LED")
      (libsource (lib "") (part "LED_2"))
    )
    (comp (ref "D254")
      (value "LED")
      (footprint "LED_0402")
      (description "Red 0402 SMD LED")
      (libsource (lib "") (part "LED_2"))
    )
    (comp (ref "D255")
      (value "LED")
      (footprint "LED_0402")
      (description "Red 0402 SMD LED")
      (libsource (lib "") (part "LED_2"))
    )
    (comp (ref "D256")
      (value "LED")
      (footprint "LED_0402")
      (description "Red 0402 SMD LED")
      (libsource (lib "") (part "LED_2"))
    )
  )
  (nets
    (net (code "1") (name "/A0") (class "Default")
      (node (ref "D1") (pin "2") (pinfunction "A_2") (pintype "passive"))
      (node (ref "D10") (pin "2") (pinfunction "A_2") (pintype "passive"))
      (node (ref "D11") (pin "2") (pinfunction "A_2") (pintype "passive"))
      (node (ref "D12") (pin "2") (pinfunction "A_2") (pintype "passive"))
      (node (ref "D13") (pin "2") (pinfunction "A_2") (pintype "passive"))
      (node (ref "D14") (pin "2") (pinfunction "A_2") (pintype "passive"))
      (node (ref "D15") (pin "2") (pinfunction "A_2") (pintype "passive"))
      (node (ref "D16") (pin "2") (pinfunction "A_2") (pintype "passive"))
      (node (ref "D2") (pin "2") (pinfunction "A_2") (pintype "passive"))
      (node (ref "D3") (pin "2") (pinfunction "A_2") (pintype "passive"))
      (node (ref "D4") (pin "2") (pinfunction "A_2") (pintype "passive"))
      (node (ref "D5") (pin "2") (pinfunction "A_2") (pintype "passive"))
      (node (ref "D6") (pin "2") (pinfunction "A_2") (pintype "passive"))
      (node (ref "D7") (pin "2") (pinfunction "A_2") (pintype "passive"))
      (node (ref "D8") (pin "2") (pinfunction "A_2") (pintype "passive"))
      (node (ref "D9") (pin "2") (pinfunction "A_2") (pintype "passive"))
    )
    (net (code "2") (name "/A1") (class "Default")
      (node (ref "D17") (pin "2") (pinfunction "A_2") (pintype "passive"))
      (node (ref "D18") (pin "2") (pinfunction "A_2") (pintype "passive"))
      (node (ref "D19") (pin "2") (pinfunction "A_2") (pintype "passive"))
      (node (ref "D20") (pin "2") (pinfunction "A_2") (pintype "passive"))
      (node (ref "D21") (pin "2") (pinfunction "A_2") (pintype "passive"))
      (node (ref "D22") (pin "2") (pinfunction "A_2") (pintype "passive"))
      (node (ref "D23") (pin "2") (pinfunction "A_2") (pintype "passive"))
      (node (ref "D24") (pin "2") (pinfunction "A_2") (pintype "passive"))
      (node (ref "D25") (pin "2") (pinfunction "A_2") (pintype "passive"))
      (node (ref "D26") (pin "2") (pinfunction "A_2") (pintype "passive"))
      (node (ref "D27") (pin "2") (pinfunction "A_2") (pintype "passive"))
      (node (ref "D28") (pin "2") (pinfunction "A_2") (pintype "passive"))
      (node (ref "D29") (pin "2") (pinfunction "A_2") (pintype "passive"))
      (node (ref "D30") (pin "2") (pinfunction "A_2") (pintype "passive"))
      (node (ref "D31") (pin "2") (pinfunction "A_2") (pintype "passive"))
      (node (ref "D32") (pin "2") (pinfunction "A_2") (pintype "passive"))
    )
    (net (code "3") (name "/A2") (class "Default")
      (node (ref "D33") (pin "2") (pinfunction "A_2") (pintype "passive"))
      (node (ref "D34") (pin "2") (pinfunction "A_2") (pintype "passive"))
      (node (ref "D35") (pin "2") (pinfunction "A_2") (pintype "passive"))
      (node (ref "D36") (pin "2") (pinfunction "A_2") (pintype "passive"))
      (node (ref "D37") (pin "2") (pinfunction "A_2") (pintype "passive"))
      (node (ref "D38") (pin "2") (pinfunction "A_2") (pintype "passive"))
      (node (ref "D39") (pin "2") (pinfunction "A_2") (pintype "passive"))
      (node (ref "D40") (pin "2") (pinfunction "A_2") (pintype "passive"))
      (node (ref "D41") (pin "2") (pinfunction "A_2") (pintype "passive"))
      (node (ref "D42") (pin "2") (pinfunction "A_2") (pintype "passive"))
      (node (ref "D43") (pin "2") (pinfunction "A_2") (pintype "passive"))
      (node (ref "D44") (pin "2") (pinfunction "A_2") (pintype "passive"))
      (node (ref "D45") (pin "2") (pinfunction "A_2") (pintype "passive"))
      (node (ref "D46") (pin "2") (pinfunction "A_2") (pintype "passive"))
      (node (ref "D47") (pin "2") (pinfunction "A_2") (pintype "passive"))
      (node (ref "D48") (pin "2") (pinfunction "A_2") (pintype "passive"))
    )
    (net (code "4") (name "/A3") (class "Default")
      (node (ref "D49") (pin "2") (pinfunction "A_2") (pintype "passive"))
      (node (ref "D50") (pin "2") (pinfunction "A_2") (pintype "passive"))
      (node (ref "D51") (pin "2") (pinfunction "A_2") (pintype "passive"))
      (node (ref "D52") (pin "2") (pinfunction "A_2") (pintype "passive"))
      (node (ref "D53") (pin "2") (pinfunction "A_2") (pintype "passive"))
      (node (ref "D54") (pin "2") (pinfunction "A_2") (pintype "passive"))
      (node (ref "D55") (pin "2") (pinfunction "A_2") (pintype "passive"))
      (node (ref "D56") (pin "2") (pinfunction "A_2") (pintype "passive"))
      (node (ref "D57") (pin "2") (pinfunction "A_2") (pintype "passive"))
      (node (ref "D58") (pin "2") (pinfunction "A_2") (pintype "passive"))
      (node (ref "D59") (pin "2") (pinfunction "A_2") (pintype "passive"))
      (node (ref "D60") (pin "2") (pinfunction "A_2") (pintype "passive"))
      (node (ref "D61") (pin "2") (pinfunction "A_2") (pintype "passive"))
      (node (ref "D62") (pin "2") (pinfunction "A_2") (pintype "passive"))
      (node (ref "D63") (pin "2") (pinfunction "A_2") (pintype "passive"))
      (node (ref "D64") (pin "2") (pinfunction "A_2") (pintype "passive"))
    )
    (net (code "5") (name "/A4") (class "Default")
      (node (ref "D65") (pin "2") (pinfunction "A_2") (pintype "passive"))
      (node (ref "D66") (pin "2") (pinfunction "A_2") (pintype "passive"))
      (node (ref "D67") (pin "2") (pinfunction "A_2") (pintype "passive"))
      (node (ref "D68") (pin "2") (pinfunction "A_2") (pintype "passive"))
      (node (ref "D69") (pin "2") (pinfunction "A_2") (pintype "passive"))
      (node (ref "D70") (pin "2") (pinfunction "A_2") (pintype "passive"))
      (node (ref "D71") (pin "2") (pinfunction "A_2") (pintype "passive"))
      (node (ref "D72") (pin "2") (pinfunction "A_2") (pintype "passive"))
      (node (ref "D73") (pin "2") (pinfunction "A_2") (pintype "passive"))
      (node (ref "D74") (pin "2") (pinfunction "A_2") (pintype "passive"))
      (node (ref "D75") (pin "2") (pinfunction "A_2") (pintype "passive"))
      (node (ref "D76") (pin "2") (pinfunction "A_2") (pintype "passive"))
      (node (ref "D77") (pin "2") (pinfunction "A_2") (pintype "passive"))
      (node (ref "D78") (pin "2") (pinfunction "A_2") (pintype "passive"))
      (node (ref "D79") (pin "2") (pinfunction "A_2") (pintype "passive"))
      (node (ref "D80") (pin "2") (pinfunction "A_2") (pintype "passive"))
    )
    (net (code "6") (name "/A5") (class "Default")
      (node (ref "D81") (pin "2") (pinfunction "A_2") (pintype "passive"))
      (node (ref "D82") (pin "2") (pinfunction "A_2") (pintype "passive"))
      (node (ref "D83") (pin "2") (pinfunction "A_2") (pintype "passive"))
      (node (ref "D84") (pin "2") (pinfunction "A_2") (pintype "passive"))
      (node (ref "D85") (pin "2") (pinfunction "A_2") (pintype "passive"))
      (node (ref "D86") (pin "2") (pinfunction "A_2") (pintype "passive"))
      (node (ref "D87") (pin "2") (pinfunction "A_2") (pintype "passive"))
      (node (ref "D88") (pin "2") (pinfunction "A_2") (pintype "passive"))
      (node (ref "D89") (pin "2") (pinfunction "A_2") (pintype "passive"))
      (node (ref "D90") (pin "2") (pinfunction "A_2") (pintype "passive"))
      (node (ref "D91") (pin "2") (pinfunction "A_2") (pintype "passive"))
      (node (ref "D92") (pin "2") (pinfunction "A_2") (pintype "passive"))
      (node (ref "D93") (pin "2") (pinfunction "A_2") (pintype "passive"))
      (node (ref "D94") (pin "2") (pinfunction "A_2") (pintype "passive"))
      (node (ref "D95") (pin "2") (pinfunction "A_2") (pintype "passive"))
      (node (ref "D96") (pin "2") (pinfunction "A_2") (pintype "passive"))
    )
    (net (code "7") (name "/A6") (class "Default")
      (node (ref "D100") (pin "2") (pinfunction "A_2") (pintype "passive"))
      (node (ref "D101") (pin "2") (pinfunction "A_2") (pintype "passive"))
      (node (ref "D102") (pin "2") (pinfunction "A_2") (pintype "passive"))
      (node (ref "D103") (pin "2") (pinfunction "A_2") (pintype "passive"))
      (node (ref "D104") (pin "2") (pinfunction "A_2") (pintype "passive"))
      (node (ref "D105") (pin "2") (pinfunction "A_2") (pintype "passive"))
      (node (ref "D106") (pin "2") (pinfunction "A_2") (pintype "passive"))
      (node (ref "D107") (pin "2") (pinfunction "A_2") (pintype "passive"))
      (node (ref "D108") (pin "2") (pinfunction "A_2") (pintype "passive"))
      (node (ref "D109") (pin "2") (pinfunction "A_2") (pintype "passive"))
      (node (ref "D110") (pin "2") (pinfunction "A_2") (pintype "passive"))
      (node (ref "D111") (pin "2") (pinfunction "A_2") (pintype "passive"))
      (node (ref "D112") (pin "2") (pinfunction "A_2") (pintype "passive"))
      (node (ref "D97") (pin "2") (pinfunction "A_2") (pintype "passive"))
      (node (ref "D98") (pin "2") (pinfunction "A_2") (pintype "passive"))
      (node (ref "D99") (pin "2") (pinfunction "A_2") (pintype "passive"))
    )
    (net (code "8") (name "/A7") (class "Default")
      (node (ref "D113") (pin "2") (pinfunction "A_2") (pintype "passive"))
      (node (ref "D114") (pin "2") (pinfunction "A_2") (pintype "passive"))
      (node (ref "D115") (pin "2") (pinfunction "A_2") (pintype "passive"))
      (node (ref "D116") (pin "2") (pinfunction "A_2") (pintype "passive"))
      (node (ref "D117") (pin "2") (pinfunction "A_2") (pintype "passive"))
      (node (ref "D118") (pin "2") (pinfunction "A_2") (pintype "passive"))
      (node (ref "D119") (pin "2") (pinfunction "A_2") (pintype "passive"))
      (node (ref "D120") (pin "2") (pinfunction "A_2") (pintype "passive"))
      (node (ref "D121") (pin "2") (pinfunction "A_2") (pintype "passive"))
      (node (ref "D122") (pin "2") (pinfunction "A_2") (pintype "passive"))
      (node (ref "D123") (pin "2") (pinfunction "A_2") (pintype "passive"))
      (node (ref "D124") (pin "2") (pinfunction "A_2") (pintype "passive"))
      (node (ref "D125") (pin "2") (pinfunction "A_2") (pintype "passive"))
      (node (ref "D126") (pin "2") (pinfunction "A_2") (pintype "passive"))
      (node (ref "D127") (pin "2") (pinfunction "A_2") (pintype "passive"))
      (node (ref "D128") (pin "2") (pinfunction "A_2") (pintype "passive"))
    )
    (net (code "9") (name "/A8") (class "Default")
      (node (ref "D129") (pin "2") (pinfunction "A_2") (pintype "passive"))
      (node (ref "D130") (pin "2") (pinfunction "A_2") (pintype "passive"))
      (node (ref "D131") (pin "2") (pinfunction "A_2") (pintype "passive"))
      (node (ref "D132") (pin "2") (pinfunction "A_2") (pintype "passive"))
      (node (ref "D133") (pin "2") (pinfunction "A_2") (pintype "passive"))
      (node (ref "D134") (pin "2") (pinfunction "A_2") (pintype "passive"))
      (node (ref "D135") (pin "2") (pinfunction "A_2") (pintype "passive"))
      (node (ref "D136") (pin "2") (pinfunction "A_2") (pintype "passive"))
      (node (ref "D137") (pin "2") (pinfunction "A_2") (pintype "passive"))
      (node (ref "D138") (pin "2") (pinfunction "A_2") (pintype "passive"))
      (node (ref "D139") (pin "2") (pinfunction "A_2") (pintype "passive"))
      (node (ref "D140") (pin "2") (pinfunction "A_2") (pintype "passive"))
      (node (ref "D141") (pin "2") (pinfunction "A_2") (pintype "passive"))
      (node (ref "D142") (pin "2") (pinfunction "A_2") (pintype "passive"))
      (node (ref "D143") (pin "2") (pinfunction "A_2") (pintype "passive"))
      (node (ref "D144") (pin "2") (pinfunction "A_2") (pintype "passive"))
    )
    (net (code "10") (name "/A9") (class "Default")
      (node (ref "D145") (pin "2") (pinfunction "A_2") (pintype "passive"))
      (node (ref "D146") (pin "2") (pinfunction "A_2") (pintype "passive"))
      (node (ref "D147") (pin "2") (pinfunction "A_2") (pintype "passive"))
      (node (ref "D148") (pin "2") (pinfunction "A_2") (pintype "passive"))
      (node (ref "D149") (pin "2") (pinfunction "A_2") (pintype "passive"))
      (node (ref "D150") (pin "2") (pinfunction "A_2") (pintype "passive"))
      (node (ref "D151") (pin "2") (pinfunction "A_2") (pintype "passive"))
      (node (ref "D152") (pin "2") (pinfunction "A_2") (pintype "passive"))
      (node (ref "D153") (pin "2") (pinfunction "A_2") (pintype "passive"))
      (node (ref "D154") (pin "2") (pinfunction "A_2") (pintype "passive"))
      (node (ref "D155") (pin "2") (pinfunction "A_2") (pintype "passive"))
      (node (ref "D156") (pin "2") (pinfunction "A_2") (pintype "passive"))
      (node (ref "D157") (pin "2") (pinfunction "A_2") (pintype "passive"))
      (node (ref "D158") (pin "2") (pinfunction "A_2") (pintype "passive"))
      (node (ref "D159") (pin "2") (pinfunction "A_2") (pintype "passive"))
      (node (ref "D160") (pin "2") (pinfunction "A_2") (pintype "passive"))
    )
    (net (code "11") (name "/A10") (class "Default")
      (node (ref "D161") (pin "2") (pinfunction "A_2") (pintype "passive"))
      (node (ref "D162") (pin "2") (pinfunction "A_2") (pintype "passive"))
      (node (ref "D163") (pin "2") (pinfunction "A_2") (pintype "passive"))
      (node (ref "D164") (pin "2") (pinfunction "A_2") (pintype "passive"))
      (node (ref "D165") (pin "2") (pinfunction "A_2") (pintype "passive"))
      (node (ref "D166") (pin "2") (pinfunction "A_2") (pintype "passive"))
      (node (ref "D167") (pin "2") (pinfunction "A_2") (pintype "passive"))
      (node (ref "D168") (pin "2") (pinfunction "A_2") (pintype "passive"))
      (node (ref "D169") (pin "2") (pinfunction "A_2") (pintype "passive"))
      (node (ref "D170") (pin "2") (pinfunction "A_2") (pintype "passive"))
      (node (ref "D171") (pin "2") (pinfunction "A_2") (pintype "passive"))
      (node (ref "D172") (pin "2") (pinfunction "A_2") (pintype "passive"))
      (node (ref "D173") (pin "2") (pinfunction "A_2") (pintype "passive"))
      (node (ref "D174") (pin "2") (pinfunction "A_2") (pintype "passive"))
      (node (ref "D175") (pin "2") (pinfunction "A_2") (pintype "passive"))
      (node (ref "D176") (pin "2") (pinfunction "A_2") (pintype "passive"))
    )
    (net (code "12") (name "/A11") (class "Default")
      (node (ref "D177") (pin "2") (pinfunction "A_2") (pintype "passive"))
      (node (ref "D178") (pin "2") (pinfunction "A_2") (pintype "passive"))
      (node (ref "D179") (pin "2") (pinfunction "A_2") (pintype "passive"))
      (node (ref "D180") (pin "2") (pinfunction "A_2") (pintype "passive"))
      (node (ref "D181") (pin "2") (pinfunction "A_2") (pintype "passive"))
      (node (ref "D182") (pin "2") (pinfunction "A_2") (pintype "passive"))
      (node (ref "D183") (pin "2") (pinfunction "A_2") (pintype "passive"))
      (node (ref "D184") (pin "2") (pinfunction "A_2") (pintype "passive"))
      (node (ref "D185") (pin "2") (pinfunction "A_2") (pintype "passive"))
      (node (ref "D186") (pin "2") (pinfunction "A_2") (pintype "passive"))
      (node (ref "D187") (pin "2") (pinfunction "A_2") (pintype "passive"))
      (node (ref "D188") (pin "2") (pinfunction "A_2") (pintype "passive"))
      (node (ref "D189") (pin "2") (pinfunction "A_2") (pintype "passive"))
      (node (ref "D190") (pin "2") (pinfunction "A_2") (pintype "passive"))
      (node (ref "D191") (pin "2") (pinfunction "A_2") (pintype "passive"))
      (node (ref "D192") (pin "2") (pinfunction "A_2") (pintype "passive"))
    )
    (net (code "13") (name "/A12") (class "Default")
      (node (ref "D193") (pin "2") (pinfunction "A_2") (pintype "passive"))
      (node (ref "D194") (pin "2") (pinfunction "A_2") (pintype "passive"))
      (node (ref "D195") (pin "2") (pinfunction "A_2") (pintype "passive"))
      (node (ref "D196") (pin "2") (pinfunction "A_2") (pintype "passive"))
      (node (ref "D197") (pin "2") (pinfunction "A_2") (pintype "passive"))
      (node (ref "D198") (pin "2") (pinfunction "A_2") (pintype "passive"))
      (node (ref "D199") (pin "2") (pinfunction "A_2") (pintype "passive"))
      (node (ref "D200") (pin "2") (pinfunction "A_2") (pintype "passive"))
      (node (ref "D201") (pin "2") (pinfunction "A_2") (pintype "passive"))
      (node (ref "D202") (pin "2") (pinfunction "A_2") (pintype "passive"))
      (node (ref "D203") (pin "2") (pinfunction "A_2") (pintype "passive"))
      (node (ref "D204") (pin "2") (pinfunction "A_2") (pintype "passive"))
      (node (ref "D205") (pin "2") (pinfunction "A_2") (pintype "passive"))
      (node (ref "D206") (pin "2") (pinfunction "A_2") (pintype "passive"))
      (node (ref "D207") (pin "2") (pinfunction "A_2") (pintype "passive"))
      (node (ref "D208") (pin "2") (pinfunction "A_2") (pintype "passive"))
    )
    (net (code "14") (name "/A13") (class "Default")
      (node (ref "D209") (pin "2") (pinfunction "A_2") (pintype "passive"))
      (node (ref "D210") (pin "2") (pinfunction "A_2") (pintype "passive"))
      (node (ref "D211") (pin "2") (pinfunction "A_2") (pintype "passive"))
      (node (ref "D212") (pin "2") (pinfunction "A_2") (pintype "passive"))
      (node (ref "D213") (pin "2") (pinfunction "A_2") (pintype "passive"))
      (node (ref "D214") (pin "2") (pinfunction "A_2") (pintype "passive"))
      (node (ref "D215") (pin "2") (pinfunction "A_2") (pintype "passive"))
      (node (ref "D216") (pin "2") (pinfunction "A_2") (pintype "passive"))
      (node (ref "D217") (pin "2") (pinfunction "A_2") (pintype "passive"))
      (node (ref "D218") (pin "2") (pinfunction "A_2") (pintype "passive"))
      (node (ref "D219") (pin "2") (pinfunction "A_2") (pintype "passive"))
      (node (ref "D220") (pin "2") (pinfunction "A_2") (pintype "passive"))
      (node (ref "D221") (pin "2") (pinfunction "A_2") (pintype "passive"))
      (node (ref "D222") (pin "2") (pinfunction "A_2") (pintype "passive"))
      (node (ref "D223") (pin "2") (pinfunction "A_2") (pintype "passive"))
      (node (ref "D224") (pin "2") (pinfunction "A_2") (pintype "passive"))
    )
    (net (code "15") (name "/A14") (class "Default")
      (node (ref "D225") (pin "2") (pinfunction "A_2") (pintype "passive"))
      (node (ref "D226") (pin "2") (pinfunction "A_2") (pintype "passive"))
      (node (ref "D227") (pin "2") (pinfunction "A_2") (pintype "passive"))
      (node (ref "D228") (pin "2") (pinfunction "A_2") (pintype "passive"))
      (node (ref "D229") (pin "2") (pinfunction "A_2") (pintype "passive"))
      (node (ref "D230") (pin "2") (pinfunction "A_2") (pintype "passive"))
      (node (ref "D231") (pin "2") (pinfunction "A_2") (pintype "passive"))
      (node (ref "D232") (pin "2") (pinfunction "A_2") (pintype "passive"))
      (node (ref "D233") (pin "2") (pinfunction "A_2") (pintype "passive"))
      (node (ref "D234") (pin "2") (pinfunction "A_2") (pintype "passive"))
      (node (ref "D235") (pin "2") (pinfunction "A_2") (pintype "passive"))
      (node (ref "D236") (pin "2") (pinfunction "A_2") (pintype "passive"))
      (node (ref "D237") (pin "2") (pinfunction "A_2") (pintype "passive"))
      (node (ref "D238") (pin "2") (pinfunction "A_2") (pintype "passive"))
      (node (ref "D239") (pin "2") (pinfunction "A_2") (pintype "passive"))
      (node (ref "D240") (pin "2") (pinfunction "A_2") (pintype "passive"))
    )
    (net (code "16") (name "/A15") (class "Default")
      (node (ref "D241") (pin "2") (pinfunction "A_2") (pintype "passive"))
      (node (ref "D242") (pin "2") (pinfunction "A_2") (pintype "passive"))
      (node (ref "D243") (pin "2") (pinfunction "A_2") (pintype "passive"))
      (node (ref "D244") (pin "2") (pinfunction "A_2") (pintype "passive"))
      (node (ref "D245") (pin "2") (pinfunction "A_2") (pintype "passive"))
      (node (ref "D246") (pin "2") (pinfunction "A_2") (pintype "passive"))
      (node (ref "D247") (pin "2") (pinfunction "A_2") (pintype "passive"))
      (node (ref "D248") (pin "2") (pinfunction "A_2") (pintype "passive"))
      (node (ref "D249") (pin "2") (pinfunction "A_2") (pintype "passive"))
      (node (ref "D250") (pin "2") (pinfunction "A_2") (pintype "passive"))
      (node (ref "D251") (pin "2") (pinfunction "A_2") (pintype "passive"))
      (node (ref "D252") (pin "2") (pinfunction "A_2") (pintype "passive"))
      (node (ref "D253") (pin "2") (pinfunction "A_2") (pintype "passive"))
      (node (ref "D254") (pin "2") (pinfunction "A_2") (pintype "passive"))
      (node (ref "D255") (pin "2") (pinfunction "A_2") (pintype "passive"))
      (node (ref "D256") (pin "2") (pinfunction "A_2") (pintype "passive"))
    )
    (net (code "18") (name "/K0") (class "Default")
      (node (ref "D1") (pin "1") (pinfunction "C_1") (pintype "passive"))
      (node (ref "D113") (pin "1") (pinfunction "C_1") (pintype "passive"))
      (node (ref "D129") (pin "1") (pinfunction "C_1") (pintype "passive"))
      (node (ref "D145") (pin "1") (pinfunction "C_1") (pintype "passive"))
      (node (ref "D161") (pin "1") (pinfunction "C_1") (pintype "passive"))
      (node (ref "D17") (pin "1") (pinfunction "C_1") (pintype "passive"))
      (node (ref "D177") (pin "1") (pinfunction "C_1") (pintype "passive"))
      (node (ref "D193") (pin "1") (pinfunction "C_1") (pintype "passive"))
      (node (ref "D209") (pin "1") (pinfunction "C_1") (pintype "passive"))
      (node (ref "D225") (pin "1") (pinfunction "C_1") (pintype "passive"))
      (node (ref "D241") (pin "1") (pinfunction "C_1") (pintype "passive"))
      (node (ref "D33") (pin "1") (pinfunction "C_1") (pintype "passive"))
      (node (ref "D49") (pin "1") (pinfunction "C_1") (pintype "passive"))
      (node (ref "D65") (pin "1") (pinfunction "C_1") (pintype "passive"))
      (node (ref "D81") (pin "1") (pinfunction "C_1") (pintype "passive"))
      (node (ref "D97") (pin "1") (pinfunction "C_1") (pintype "passive"))
    )
    (net (code "19") (name "/K1") (class "Default")
      (node (ref "D114") (pin "1") (pinfunction "C_1") (pintype "passive"))
      (node (ref "D130") (pin "1") (pinfunction "C_1") (pintype "passive"))
      (node (ref "D146") (pin "1") (pinfunction "C_1") (pintype "passive"))
      (node (ref "D162") (pin "1") (pinfunction "C_1") (pintype "passive"))
      (node (ref "D178") (pin "1") (pinfunction "C_1") (pintype "passive"))
      (node (ref "D18") (pin "1") (pinfunction "C_1") (pintype "passive"))
      (node (ref "D194") (pin "1") (pinfunction "C_1") (pintype "passive"))
      (node (ref "D2") (pin "1") (pinfunction "C_1") (pintype "passive"))
      (node (ref "D210") (pin "1") (pinfunction "C_1") (pintype "passive"))
      (node (ref "D226") (pin "1") (pinfunction "C_1") (pintype "passive"))
      (node (ref "D242") (pin "1") (pinfunction "C_1") (pintype "passive"))
      (node (ref "D34") (pin "1") (pinfunction "C_1") (pintype "passive"))
      (node (ref "D50") (pin "1") (pinfunction "C_1") (pintype "passive"))
      (node (ref "D66") (pin "1") (pinfunction "C_1") (pintype "passive"))
      (node (ref "D82") (pin "1") (pinfunction "C_1") (pintype "passive"))
      (node (ref "D98") (pin "1") (pinfunction "C_1") (pintype "passive"))
    )
    (net (code "20") (name "/K2") (class "Default")
      (node (ref "D115") (pin "1") (pinfunction "C_1") (pintype "passive"))
      (node (ref "D131") (pin "1") (pinfunction "C_1") (pintype "passive"))
      (node (ref "D147") (pin "1") (pinfunction "C_1") (pintype "passive"))
      (node (ref "D163") (pin "1") (pinfunction "C_1") (pintype "passive"))
      (node (ref "D179") (pin "1") (pinfunction "C_1") (pintype "passive"))
      (node (ref "D19") (pin "1") (pinfunction "C_1") (pintype "passive"))
      (node (ref "D195") (pin "1") (pinfunction "C_1") (pintype "passive"))
      (node (ref "D211") (pin "1") (pinfunction "C_1") (pintype "passive"))
      (node (ref "D227") (pin "1") (pinfunction "C_1") (pintype "passive"))
      (node (ref "D243") (pin "1") (pinfunction "C_1") (pintype "passive"))
      (node (ref "D3") (pin "1") (pinfunction "C_1") (pintype "passive"))
      (node (ref "D35") (pin "1") (pinfunction "C_1") (pintype "passive"))
      (node (ref "D51") (pin "1") (pinfunction "C_1") (pintype "passive"))
      (node (ref "D67") (pin "1") (pinfunction "C_1") (pintype "passive"))
      (node (ref "D83") (pin "1") (pinfunction "C_1") (pintype "passive"))
      (node (ref "D99") (pin "1") (pinfunction "C_1") (pintype "passive"))
    )
    (net (code "21") (name "/K3") (class "Default")
      (node (ref "D100") (pin "1") (pinfunction "C_1") (pintype "passive"))
      (node (ref "D116") (pin "1") (pinfunction "C_1") (pintype "passive"))
      (node (ref "D132") (pin "1") (pinfunction "C_1") (pintype "passive"))
      (node (ref "D148") (pin "1") (pinfunction "C_1") (pintype "passive"))
      (node (ref "D164") (pin "1") (pinfunction "C_1") (pintype "passive"))
      (node (ref "D180") (pin "1") (pinfunction "C_1") (pintype "passive"))
      (node (ref "D196") (pin "1") (pinfunction "C_1") (pintype "passive"))
      (node (ref "D20") (pin "1") (pinfunction "C_1") (pintype "passive"))
      (node (ref "D212") (pin "1") (pinfunction "C_1") (pintype "passive"))
      (node (ref "D228") (pin "1") (pinfunction "C_1") (pintype "passive"))
      (node (ref "D244") (pin "1") (pinfunction "C_1") (pintype "passive"))
      (node (ref "D36") (pin "1") (pinfunction "C_1") (pintype "passive"))
      (node (ref "D4") (pin "1") (pinfunction "C_1") (pintype "passive"))
      (node (ref "D52") (pin "1") (pinfunction "C_1") (pintype "passive"))
      (node (ref "D68") (pin "1") (pinfunction "C_1") (pintype "passive"))
      (node (ref "D84") (pin "1") (pinfunction "C_1") (pintype "passive"))
    )
    (net (code "22") (name "/K4") (class "Default")
      (node (ref "D101") (pin "1") (pinfunction "C_1") (pintype "passive"))
      (node (ref "D117") (pin "1") (pinfunction "C_1") (pintype "passive"))
      (node (ref "D133") (pin "1") (pinfunction "C_1") (pintype "passive"))
      (node (ref "D149") (pin "1") (pinfunction "C_1") (pintype "passive"))
      (node (ref "D165") (pin "1") (pinfunction "C_1") (pintype "passive"))
      (node (ref "D181") (pin "1") (pinfunction "C_1") (pintype "passive"))
      (node (ref "D197") (pin "1") (pinfunction "C_1") (pintype "passive"))
      (node (ref "D21") (pin "1") (pinfunction "C_1") (pintype "passive"))
      (node (ref "D213") (pin "1") (pinfunction "C_1") (pintype "passive"))
      (node (ref "D229") (pin "1") (pinfunction "C_1") (pintype "passive"))
      (node (ref "D245") (pin "1") (pinfunction "C_1") (pintype "passive"))
      (node (ref "D37") (pin "1") (pinfunction "C_1") (pintype "passive"))
      (node (ref "D5") (pin "1") (pinfunction "C_1") (pintype "passive"))
      (node (ref "D53") (pin "1") (pinfunction "C_1") (pintype "passive"))
      (node (ref "D69") (pin "1") (pinfunction "C_1") (pintype "passive"))
      (node (ref "D85") (pin "1") (pinfunction "C_1") (pintype "passive"))
    )
    (net (code "23") (name "/K5") (class "Default")
      (node (ref "D102") (pin "1") (pinfunction "C_1") (pintype "passive"))
      (node (ref "D118") (pin "1") (pinfunction "C_1") (pintype "passive"))
      (node (ref "D134") (pin "1") (pinfunction "C_1") (pintype "passive"))
      (node (ref "D150") (pin "1") (pinfunction "C_1") (pintype "passive"))
      (node (ref "D166") (pin "1") (pinfunction "C_1") (pintype "passive"))
      (node (ref "D182") (pin "1") (pinfunction "C_1") (pintype "passive"))
      (node (ref "D198") (pin "1") (pinfunction "C_1") (pintype "passive"))
      (node (ref "D214") (pin "1") (pinfunction "C_1") (pintype "passive"))
      (node (ref "D22") (pin "1") (pinfunction "C_1") (pintype "passive"))
      (node (ref "D230") (pin "1") (pinfunction "C_1") (pintype "passive"))
      (node (ref "D246") (pin "1") (pinfunction "C_1") (pintype "passive"))
      (node (ref "D38") (pin "1") (pinfunction "C_1") (pintype "passive"))
      (node (ref "D54") (pin "1") (pinfunction "C_1") (pintype "passive"))
      (node (ref "D6") (pin "1") (pinfunction "C_1") (pintype "passive"))
      (node (ref "D70") (pin "1") (pinfunction "C_1") (pintype "passive"))
      (node (ref "D86") (pin "1") (pinfunction "C_1") (pintype "passive"))
    )
    (net (code "24") (name "/K6") (class "Default")
      (node (ref "D103") (pin "1") (pinfunction "C_1") (pintype "passive"))
      (node (ref "D119") (pin "1") (pinfunction "C_1") (pintype "passive"))
      (node (ref "D135") (pin "1") (pinfunction "C_1") (pintype "passive"))
      (node (ref "D151") (pin "1") (pinfunction "C_1") (pintype "passive"))
      (node (ref "D167") (pin "1") (pinfunction "C_1") (pintype "passive"))
      (node (ref "D183") (pin "1") (pinfunction "C_1") (pintype "passive"))
      (node (ref "D199") (pin "1") (pinfunction "C_1") (pintype "passive"))
      (node (ref "D215") (pin "1") (pinfunction "C_1") (pintype "passive"))
      (node (ref "D23") (pin "1") (pinfunction "C_1") (pintype "passive"))
      (node (ref "D231") (pin "1") (pinfunction "C_1") (pintype "passive"))
      (node (ref "D247") (pin "1") (pinfunction "C_1") (pintype "passive"))
      (node (ref "D39") (pin "1") (pinfunction "C_1") (pintype "passive"))
      (node (ref "D55") (pin "1") (pinfunction "C_1") (pintype "passive"))
      (node (ref "D7") (pin "1") (pinfunction "C_1") (pintype "passive"))
      (node (ref "D71") (pin "1") (pinfunction "C_1") (pintype "passive"))
      (node (ref "D87") (pin "1") (pinfunction "C_1") (pintype "passive"))
    )
    (net (code "25") (name "/K7") (class "Default")
      (node (ref "D104") (pin "1") (pinfunction "C_1") (pintype "passive"))
      (node (ref "D120") (pin "1") (pinfunction "C_1") (pintype "passive"))
      (node (ref "D136") (pin "1") (pinfunction "C_1") (pintype "passive"))
      (node (ref "D152") (pin "1") (pinfunction "C_1") (pintype "passive"))
      (node (ref "D168") (pin "1") (pinfunction "C_1") (pintype "passive"))
      (node (ref "D184") (pin "1") (pinfunction "C_1") (pintype "passive"))
      (node (ref "D200") (pin "1") (pinfunction "C_1") (pintype "passive"))
      (node (ref "D216") (pin "1") (pinfunction "C_1") (pintype "passive"))
      (node (ref "D232") (pin "1") (pinfunction "C_1") (pintype "passive"))
      (node (ref "D24") (pin "1") (pinfunction "C_1") (pintype "passive"))
      (node (ref "D248") (pin "1") (pinfunction "C_1") (pintype "passive"))
      (node (ref "D40") (pin "1") (pinfunction "C_1") (pintype "passive"))
      (node (ref "D56") (pin "1") (pinfunction "C_1") (pintype "passive"))
      (node (ref "D72") (pin "1") (pinfunction "C_1") (pintype "passive"))
      (node (ref "D8") (pin "1") (pinfunction "C_1") (pintype "passive"))
      (node (ref "D88") (pin "1") (pinfunction "C_1") (pintype "passive"))
    )
    (net (code "26") (name "/K8") (class "Default")
      (node (ref "D105") (pin "1") (pinfunction "C_1") (pintype "passive"))
      (node (ref "D121") (pin "1") (pinfunction "C_1") (pintype "passive"))
      (node (ref "D137") (pin "1") (pinfunction "C_1") (pintype "passive"))
      (node (ref "D153") (pin "1") (pinfunction "C_1") (pintype "passive"))
      (node (ref "D169") (pin "1") (pinfunction "C_1") (pintype "passive"))
      (node (ref "D185") (pin "1") (pinfunction "C_1") (pintype "passive"))
      (node (ref "D201") (pin "1") (pinfunction "C_1") (pintype "passive"))
      (node (ref "D217") (pin "1") (pinfunction "C_1") (pintype "passive"))
      (node (ref "D233") (pin "1") (pinfunction "C_1") (pintype "passive"))
      (node (ref "D249") (pin "1") (pinfunction "C_1") (pintype "passive"))
      (node (ref "D25") (pin "1") (pinfunction "C_1") (pintype "passive"))
      (node (ref "D41") (pin "1") (pinfunction "C_1") (pintype "passive"))
      (node (ref "D57") (pin "1") (pinfunction "C_1") (pintype "passive"))
      (node (ref "D73") (pin "1") (pinfunction "C_1") (pintype "passive"))
      (node (ref "D89") (pin "1") (pinfunction "C_1") (pintype "passive"))
      (node (ref "D9") (pin "1") (pinfunction "C_1") (pintype "passive"))
    )
    (net (code "27") (name "/K9") (class "Default")
      (node (ref "D10") (pin "1") (pinfunction "C_1") (pintype "passive"))
      (node (ref "D106") (pin "1") (pinfunction "C_1") (pintype "passive"))
      (node (ref "D122") (pin "1") (pinfunction "C_1") (pintype "passive"))
      (node (ref "D138") (pin "1") (pinfunction "C_1") (pintype "passive"))
      (node (ref "D154") (pin "1") (pinfunction "C_1") (pintype "passive"))
      (node (ref "D170") (pin "1") (pinfunction "C_1") (pintype "passive"))
      (node (ref "D186") (pin "1") (pinfunction "C_1") (pintype "passive"))
      (node (ref "D202") (pin "1") (pinfunction "C_1") (pintype "passive"))
      (node (ref "D218") (pin "1") (pinfunction "C_1") (pintype "passive"))
      (node (ref "D234") (pin "1") (pinfunction "C_1") (pintype "passive"))
      (node (ref "D250") (pin "1") (pinfunction "C_1") (pintype "passive"))
      (node (ref "D26") (pin "1") (pinfunction "C_1") (pintype "passive"))
      (node (ref "D42") (pin "1") (pinfunction "C_1") (pintype "passive"))
      (node (ref "D58") (pin "1") (pinfunction "C_1") (pintype "passive"))
      (node (ref "D74") (pin "1") (pinfunction "C_1") (pintype "passive"))
      (node (ref "D90") (pin "1") (pinfunction "C_1") (pintype "passive"))
    )
    (net (code "28") (name "/K10") (class "Default")
      (node (ref "D107") (pin "1") (pinfunction "C_1") (pintype "passive"))
      (node (ref "D11") (pin "1") (pinfunction "C_1") (pintype "passive"))
      (node (ref "D123") (pin "1") (pinfunction "C_1") (pintype "passive"))
      (node (ref "D139") (pin "1") (pinfunction "C_1") (pintype "passive"))
      (node (ref "D155") (pin "1") (pinfunction "C_1") (pintype "passive"))
      (node (ref "D171") (pin "1") (pinfunction "C_1") (pintype "passive"))
      (node (ref "D187") (pin "1") (pinfunction "C_1") (pintype "passive"))
      (node (ref "D203") (pin "1") (pinfunction "C_1") (pintype "passive"))
      (node (ref "D219") (pin "1") (pinfunction "C_1") (pintype "passive"))
      (node (ref "D235") (pin "1") (pinfunction "C_1") (pintype "passive"))
      (node (ref "D251") (pin "1") (pinfunction "C_1") (pintype "passive"))
      (node (ref "D27") (pin "1") (pinfunction "C_1") (pintype "passive"))
      (node (ref "D43") (pin "1") (pinfunction "C_1") (pintype "passive"))
      (node (ref "D59") (pin "1") (pinfunction "C_1") (pintype "passive"))
      (node (ref "D75") (pin "1") (pinfunction "C_1") (pintype "passive"))
      (node (ref "D91") (pin "1") (pinfunction "C_1") (pintype "passive"))
    )
    (net (code "29") (name "/K11") (class "Default")
      (node (ref "D108") (pin "1") (pinfunction "C_1") (pintype "passive"))
      (node (ref "D12") (pin "1") (pinfunction "C_1") (pintype "passive"))
      (node (ref "D124") (pin "1") (pinfunction "C_1") (pintype "passive"))
      (node (ref "D140") (pin "1") (pinfunction "C_1") (pintype "passive"))
      (node (ref "D156") (pin "1") (pinfunction "C_1") (pintype "passive"))
      (node (ref "D172") (pin "1") (pinfunction "C_1") (pintype "passive"))
      (node (ref "D188") (pin "1") (pinfunction "C_1") (pintype "passive"))
      (node (ref "D204") (pin "1") (pinfunction "C_1") (pintype "passive"))
      (node (ref "D220") (pin "1") (pinfunction "C_1") (pintype "passive"))
      (node (ref "D236") (pin "1") (pinfunction "C_1") (pintype "passive"))
      (node (ref "D252") (pin "1") (pinfunction "C_1") (pintype "passive"))
      (node (ref "D28") (pin "1") (pinfunction "C_1") (pintype "passive"))
      (node (ref "D44") (pin "1") (pinfunction "C_1") (pintype "passive"))
      (node (ref "D60") (pin "1") (pinfunction "C_1") (pintype "passive"))
      (node (ref "D76") (pin "1") (pinfunction "C_1") (pintype "passive"))
      (node (ref "D92") (pin "1") (pinfunction "C_1") (pintype "passive"))
    )
    (net (code "30") (name "/K12") (class "Default")
      (node (ref "D109") (pin "1") (pinfunction "C_1") (pintype "passive"))
      (node (ref "D125") (pin "1") (pinfunction "C_1") (pintype "passive"))
      (node (ref "D13") (pin "1") (pinfunction "C_1") (pintype "passive"))
      (node (ref "D141") (pin "1") (pinfunction "C_1") (pintype "passive"))
      (node (ref "D157") (pin "1") (pinfunction "C_1") (pintype "passive"))
      (node (ref "D173") (pin "1") (pinfunction "C_1") (pintype "passive"))
      (node (ref "D189") (pin "1") (pinfunction "C_1") (pintype "passive"))
      (node (ref "D205") (pin "1") (pinfunction "C_1") (pintype "passive"))
      (node (ref "D221") (pin "1") (pinfunction "C_1") (pintype "passive"))
      (node (ref "D237") (pin "1") (pinfunction "C_1") (pintype "passive"))
      (node (ref "D253") (pin "1") (pinfunction "C_1") (pintype "passive"))
      (node (ref "D29") (pin "1") (pinfunction "C_1") (pintype "passive"))
      (node (ref "D45") (pin "1") (pinfunction "C_1") (pintype "passive"))
      (node (ref "D61") (pin "1") (pinfunction "C_1") (pintype "passive"))
      (node (ref "D77") (pin "1") (pinfunction "C_1") (pintype "passive"))
      (node (ref "D93") (pin "1") (pinfunction "C_1") (pintype "passive"))
    )
    (net (code "31") (name "/K13") (class "Default")
      (node (ref "D110") (pin "1") (pinfunction "C_1") (pintype "passive"))
      (node (ref "D126") (pin "1") (pinfunction "C_1") (pintype "passive"))
      (node (ref "D14") (pin "1") (pinfunction "C_1") (pintype "passive"))
      (node (ref "D142") (pin "1") (pinfunction "C_1") (pintype "passive"))
      (node (ref "D158") (pin "1") (pinfunction "C_1") (pintype "passive"))
      (node (ref "D174") (pin "1") (pinfunction "C_1") (pintype "passive"))
      (node (ref "D190") (pin "1") (pinfunction "C_1") (pintype "passive"))
      (node (ref "D206") (pin "1") (pinfunction "C_1") (pintype "passive"))
      (node (ref "D222") (pin "1") (pinfunction "C_1") (pintype "passive"))
      (node (ref "D238") (pin "1") (pinfunction "C_1") (pintype "passive"))
      (node (ref "D254") (pin "1") (pinfunction "C_1") (pintype "passive"))
      (node (ref "D30") (pin "1") (pinfunction "C_1") (pintype "passive"))
      (node (ref "D46") (pin "1") (pinfunction "C_1") (pintype "passive"))
      (node (ref "D62") (pin "1") (pinfunction "C_1") (pintype "passive"))
      (node (ref "D78") (pin "1") (pinfunction "C_1") (pintype "passive"))
      (node (ref "D94") (pin "1") (pinfunction "C_1") (pintype "passive"))
    )
    (net (code "32") (name "/K14") (class "Default")
      (node (ref "D111") (pin "1") (pinfunction "C_1") (pintype "passive"))
      (node (ref "D127") (pin "1") (pinfunction "C_1") (pintype "passive"))
      (node (ref "D143") (pin "1") (pinfunction "C_1") (pintype "passive"))
      (node (ref "D15") (pin "1") (pinfunction "C_1") (pintype "passive"))
      (node (ref "D159") (pin "1") (pinfunction "C_1") (pintype "passive"))
      (node (ref "D175") (pin "1") (pinfunction "C_1") (pintype "passive"))
      (node (ref "D191") (pin "1") (pinfunction "C_1") (pintype "passive"))
      (node (ref "D207") (pin "1") (pinfunction "C_1") (pintype "passive"))
      (node (ref "D223") (pin "1") (pinfunction "C_1") (pintype "passive"))
      (node (ref "D239") (pin "1") (pinfunction "C_1") (pintype "passive"))
      (node (ref "D255") (pin "1") (pinfunction "C_1") (pintype "passive"))
      (node (ref "D31") (pin "1") (pinfunction "C_1") (pintype "passive"))
      (node (ref "D47") (pin "1") (pinfunction "C_1") (pintype "passive"))
      (node (ref "D63") (pin "1") (pinfunction "C_1") (pintype "passive"))
      (node (ref "D79") (pin "1") (pinfunction "C_1") (pintype "passive"))
      (node (ref "D95") (pin "1") (pinfunction "C_1") (pintype "passive"))
    )
    (net (code "33") (name "/K15") (class "Default")
      (node (ref "D112") (pin "1") (pinfunction "C_1") (pintype "passive"))
      (node (ref "D128") (pin "1") (pinfunction "C_1") (pintype "passive"))
      (node (ref "D144") (pin "1") (pinfunction "C_1") (pintype "passive"))
      (node (ref "D16") (pin "1") (pinfunction "C_1") (pintype "passive"))
      (node (ref "D160") (pin "1") (pinfunction "C_1") (pintype "passive"))
      (node (ref "D176") (pin "1") (pinfunction "C_1") (pintype "passive"))
      (node (ref "D192") (pin "1") (pinfunction "C_1") (pintype "passive"))
      (node (ref "D208") (pin "1") (pinfunction "C_1") (pintype "passive"))
      (node (ref "D224") (pin "1") (pinfunction "C_1") (pintype "passive"))
      (node (ref "D240") (pin "1") (pinfunction "C_1") (pintype "passive"))
      (node (ref "D256") (pin "1") (pinfunction "C_1") (pintype "passive"))
      (node (ref "D32") (pin "1") (pinfunction "C_1") (pintype "passive"))
      (node (ref "D48") (pin "1") (pinfunction "C_1") (pintype "passive"))
      (node (ref "D64") (pin "1") (pinfunction "C_1") (pintype "passive"))
      (node (ref "D80") (pin "1") (pinfunction "C_1") (pintype "passive"))
      (node (ref "D96") (pin "1") (pinfunction "C_1") (pintype "passive"))
    )
  )
)
